# Current_Sensors.net
KiCad netlist of a schematic drawn in Altium Designer
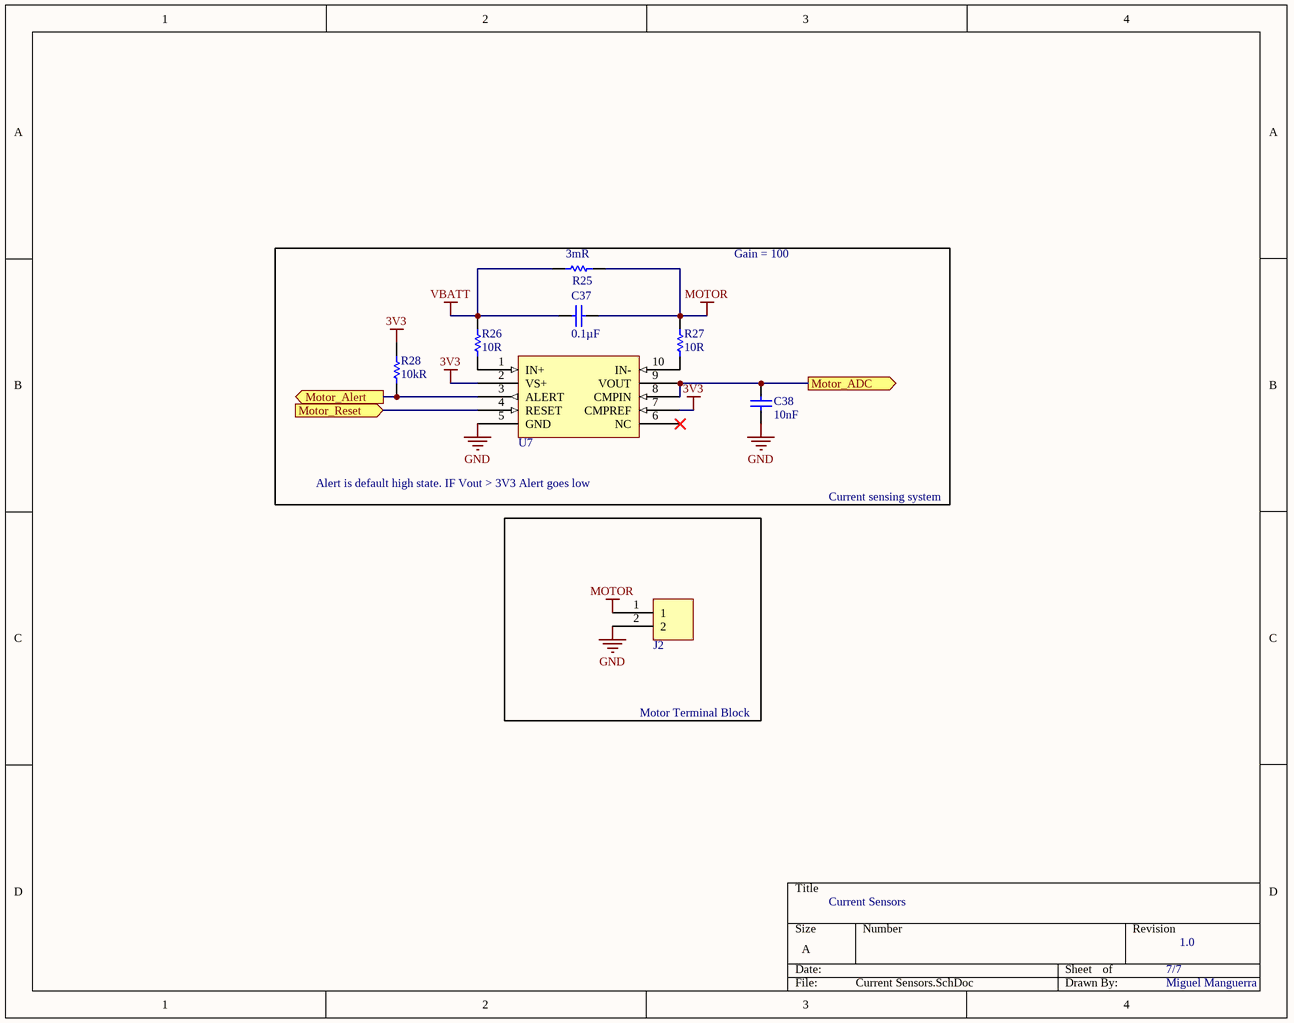
[diagram p0: Current Sensors.SchDoc]

(export (version "E")
  (design (tool "Eeschema 10.0.6"))
  (components
    (comp (ref "C37")
      (value "0.1uF, 50V, 10%, X7R, 0603")
      (footprint "CAPC1608N(0603\")")
      (description "0.1µF ±10% Ceramic Capacitor X7R 0603 (1608 Metric)")
      (fields
        (field (name "CAPACITANCE") "0.1µF")
        (field (name "SOURCE") "AUVic_Schematic_Library_Capacitors.SchLib")
        (field (name "CREATED BY") "Poorna Chander Kalidas")
      )
      (libsource (lib "AUVIC") (part "Symbol"))
    )
    (comp (ref "C38")
      (value "10nF")
      (footprint "CAPC1608N(0603\")")
      (description "Capacitor, Ceramic, 50V, +/- 10%, 0603 SMD")
      (fields
        (field (name "MFG") "Samsung")
        (field (name "Comment") "10 nF, 50V 0603 SMD, Ceramic")
        (field (name "CREATED BY") "Gabriel")
        (field (name "SOURCE") "AUVic_Schematic_Library_Capacitors.SchLib")
        (field (name "PUBLISHER") "AUVic")
      )
      (libsource (lib "AUVIC") (part "Symbol"))
    )
    (comp (ref "J2")
      (value "2x1 Terminal Block 3.5mm")
      (footprint "2x1 Terminal Block 3.5mm-Footprint-1")
      (description "P=3.5mm Screw terminal RoHS")
      (fields (field (name "LCSC PART #") "C474892") (field (name "CREATED BY") "Miguel Manguerra"))
      (libsource (lib "AUVIC") (part "2x1 Terminal Block 3.5mm"))
    )
    (comp (ref "R25")
      (value "3mR, 1%, 1W, 1206")
      (footprint "RESC1632X07M")
      (description "3 mOhms ±1% 1W Chip Resistor Wide 1206 (3216 Metric), 0612")
      (fields (field (name "RESISTANCE") "3mR"))
      (libsource (lib "AUVIC") (part "3mR"))
    )
    (comp (ref "R26")
      (value "ERJ3EKF10R0V")
      (footprint "FP-ERJ3EK-IPC_A")
      (fields (field (name "RESISTANCE") "10R") (field (name "TOLERANCE") "1%"))
      (libsource (lib "AUVIC") (part "RES"))
    )
    (comp (ref "R27")
      (value "ERJ3EKF10R0V")
      (footprint "FP-ERJ3EK-IPC_A")
      (fields (field (name "RESISTANCE") "10R") (field (name "TOLERANCE") "1%"))
      (libsource (lib "AUVIC") (part "RES"))
    )
    (comp (ref "R28")
      (value "RC0603FR-0710KL")
      (footprint "RESC1608X55X25ML10T15")
      (description "Res General Purpose Thick Film 0603 10K Ohm 1% 1/10W ±100ppm/°C Molded SMD Paper T/R")
      (fields (field (name "RESISTANCE") "10kR") (field (name "TOLERANCE") "1%"))
      (libsource (lib "AUVIC") (part "RES-2"))
    )
    (comp (ref "U7")
      (value "INA381A3IDGSR")
      (footprint "TSSOP50P490X110-10N")
      (description "26V, 350kHz current sense amplifier w/ integrated over-current comparator 10-VSSOP -40 to 125")
      (libsource (lib "AUVIC") (part "INA381A3IDGSR"))
    )
  )
  (nets
    (net (code "1") (name "/Motor_ADC") (class "Default")
      (node (ref "C38") (pin "2") (pinfunction "Cathode_2") (pintype "passive"))
      (node (ref "U7") (pin "8") (pinfunction "CMPIN_8") (pintype "input"))
      (node (ref "U7") (pin "9") (pinfunction "VOUT_9") (pintype "power_in"))
    )
    (net (code "2") (name "/Motor_Alert") (class "Default")
      (node (ref "R28") (pin "1") (pinfunction "1_1") (pintype "passive"))
      (node (ref "U7") (pin "3") (pinfunction "ALERT_3") (pintype "output"))
    )
    (net (code "3") (name "/Motor_Reset") (class "Default")
      (node (ref "U7") (pin "4") (pinfunction "RESET_4") (pintype "input"))
    )
    (net (code "4") (name "3V3") (class "Default")
      (node (ref "R28") (pin "2") (pinfunction "2_2") (pintype "passive"))
      (node (ref "U7") (pin "2") (pinfunction "VS+_2") (pintype "power_in"))
      (node (ref "U7") (pin "7") (pinfunction "CMPREF_7") (pintype "input"))
    )
    (net (code "5") (name "GND") (class "Default")
      (node (ref "C38") (pin "1") (pinfunction "Anode_1") (pintype "passive"))
      (node (ref "J2") (pin "2") (pinfunction "2_2") (pintype "power_in"))
      (node (ref "U7") (pin "5") (pinfunction "GND_5") (pintype "power_in"))
    )
    (net (code "6") (name "MOTOR") (class "Default")
      (node (ref "C37") (pin "1") (pinfunction "Anode_1") (pintype "passive"))
      (node (ref "J2") (pin "1") (pinfunction "1_1") (pintype "power_in"))
      (node (ref "R25") (pin "2") (pinfunction "2_2") (pintype "passive"))
      (node (ref "R27") (pin "2") (pinfunction "2_2") (pintype "passive"))
    )
    (net (code "7") (name "Net-(U7-IN+)") (class "Default")
      (node (ref "R26") (pin "1") (pinfunction "1_1") (pintype "passive"))
      (node (ref "U7") (pin "1") (pinfunction "IN+_1") (pintype "input"))
    )
    (net (code "8") (name "Net-(U7-IN-)") (class "Default")
      (node (ref "R27") (pin "1") (pinfunction "1_1") (pintype "passive"))
      (node (ref "U7") (pin "10") (pinfunction "IN-_10") (pintype "input"))
    )
    (net (code "9") (name "VBATT") (class "Default")
      (node (ref "C37") (pin "2") (pinfunction "Cathode_2") (pintype "passive"))
      (node (ref "R25") (pin "1") (pinfunction "1_1") (pintype "passive"))
      (node (ref "R26") (pin "2") (pinfunction "2_2") (pintype "passive"))
    )
    (net (code "10") (name "unconnected-(U7-NC-Pad6)") (class "Default")
      (node (ref "U7") (pin "6") (pinfunction "NC_6") (pintype "passive+no_connect"))
    )
  )
)
